# 3_Memory.net
KiCad netlist of a schematic drawn in Altium Designer
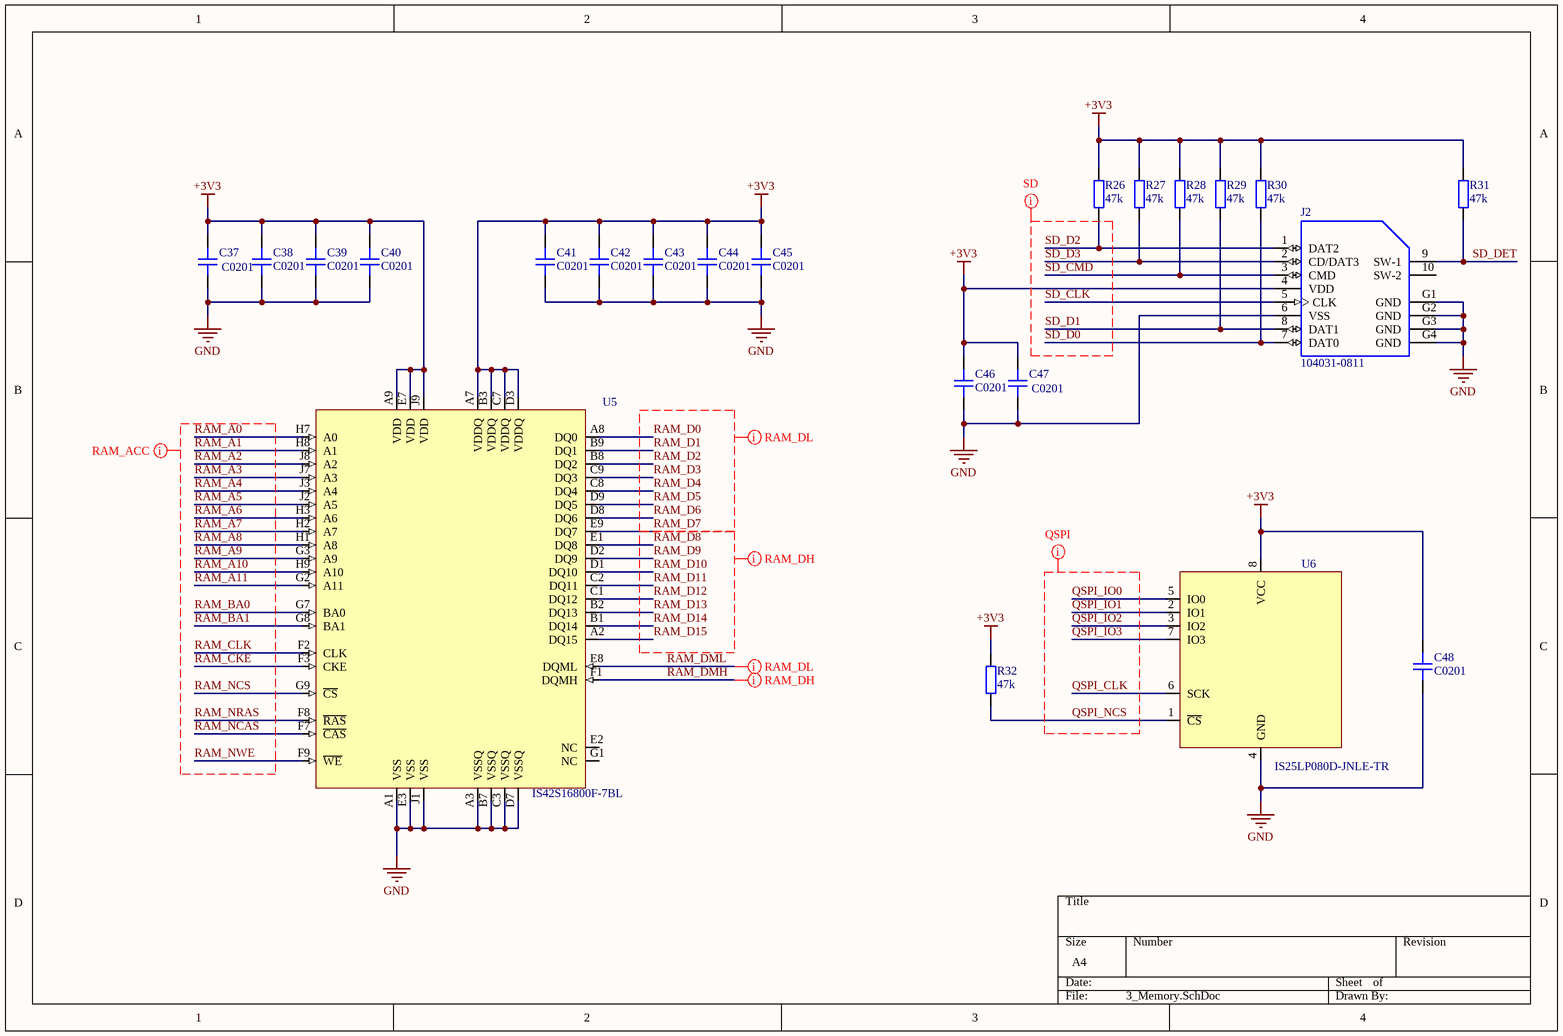
[diagram p0: 3_Memory.SchDoc]

(export (version "E")
  (design (tool "Eeschema 10.0.6"))
  (components
    (comp (ref "C37")
      (value "C0201")
      (footprint "CAP_0201")
      (description "Capacitor SMD 0201")
      (libsource (lib "Schematic-Lib-PhilsLab") (part "CAP_0201"))
    )
    (comp (ref "C38")
      (value "C0201")
      (footprint "CAP_0201")
      (description "Capacitor SMD 0201")
      (libsource (lib "Schematic-Lib-PhilsLab") (part "CAP_0201"))
    )
    (comp (ref "C39")
      (value "C0201")
      (footprint "CAP_0201")
      (description "Capacitor SMD 0201")
      (libsource (lib "Schematic-Lib-PhilsLab") (part "CAP_0201"))
    )
    (comp (ref "C40")
      (value "C0201")
      (footprint "CAP_0201")
      (description "Capacitor SMD 0201")
      (libsource (lib "Schematic-Lib-PhilsLab") (part "CAP_0201"))
    )
    (comp (ref "C41")
      (value "C0201")
      (footprint "CAP_0201")
      (description "Capacitor SMD 0201")
      (libsource (lib "Schematic-Lib-PhilsLab") (part "CAP_0201"))
    )
    (comp (ref "C42")
      (value "C0201")
      (footprint "CAP_0201")
      (description "Capacitor SMD 0201")
      (libsource (lib "Schematic-Lib-PhilsLab") (part "CAP_0201"))
    )
    (comp (ref "C43")
      (value "C0201")
      (footprint "CAP_0201")
      (description "Capacitor SMD 0201")
      (libsource (lib "Schematic-Lib-PhilsLab") (part "CAP_0201"))
    )
    (comp (ref "C44")
      (value "C0201")
      (footprint "CAP_0201")
      (description "Capacitor SMD 0201")
      (libsource (lib "Schematic-Lib-PhilsLab") (part "CAP_0201"))
    )
    (comp (ref "C45")
      (value "C0201")
      (footprint "CAP_0201")
      (description "Capacitor SMD 0201")
      (libsource (lib "Schematic-Lib-PhilsLab") (part "CAP_0201"))
    )
    (comp (ref "C46")
      (value "C0201")
      (footprint "CAP_0201")
      (description "Capacitor SMD 0201")
      (libsource (lib "Schematic-Lib-PhilsLab") (part "CAP_0201"))
    )
    (comp (ref "C47")
      (value "C0201")
      (footprint "CAP_0201")
      (description "Capacitor SMD 0201")
      (libsource (lib "Schematic-Lib-PhilsLab") (part "CAP_0201"))
    )
    (comp (ref "C48")
      (value "C0201")
      (footprint "CAP_0201")
      (description "Capacitor SMD 0201")
      (libsource (lib "Schematic-Lib-PhilsLab") (part "CAP_0201"))
    )
    (comp (ref "J2")
      (value "104031-0811")
      (footprint "104031-0811")
      (libsource (lib "SCHLib") (part "104031-0811"))
    )
    (comp (ref "R26")
      (value "47k")
      (footprint "RES_0402")
      (description "Resistor SMD 0402")
      (libsource (lib "Schematic-Lib-PhilsLab") (part "RES_0402"))
    )
    (comp (ref "R27")
      (value "47k")
      (footprint "RES_0402")
      (description "Resistor SMD 0402")
      (libsource (lib "Schematic-Lib-PhilsLab") (part "RES_0402"))
    )
    (comp (ref "R28")
      (value "47k")
      (footprint "RES_0402")
      (description "Resistor SMD 0402")
      (libsource (lib "Schematic-Lib-PhilsLab") (part "RES_0402"))
    )
    (comp (ref "R29")
      (value "47k")
      (footprint "RES_0402")
      (description "Resistor SMD 0402")
      (libsource (lib "Schematic-Lib-PhilsLab") (part "RES_0402"))
    )
    (comp (ref "R30")
      (value "47k")
      (footprint "RES_0402")
      (description "Resistor SMD 0402")
      (libsource (lib "Schematic-Lib-PhilsLab") (part "RES_0402"))
    )
    (comp (ref "R31")
      (value "47k")
      (footprint "RES_0402")
      (description "Resistor SMD 0402")
      (libsource (lib "Schematic-Lib-PhilsLab") (part "RES_0402"))
    )
    (comp (ref "R32")
      (value "47k")
      (footprint "RES_0402")
      (description "Resistor SMD 0402")
      (libsource (lib "Schematic-Lib-PhilsLab") (part "RES_0402"))
    )
    (comp (ref "U5")
      (value "IS42S16800F-7BL")
      (footprint "BGA54C80P9X9_800X800X120")
      (description "SDRAM 128Mbit 8Mx16 143Mhz 3.3V 54-ball BGA")
      (fields
        (field (name "MANUFACTURER") "ISSI")
        (field (name "MANUFACTURER PART NUMBER") "IS42S16800F-*B*")
      )
      (libsource (lib "Schematic-Lib-PhilsLab") (part "IS42S16800F-*B"))
    )
    (comp (ref "U6")
      (value "IS25LP080D-JNLE-TR")
      (footprint "SOIC-8")
      (description "QSPI NOR Flash Memory 8 Mbit SOIC-8")
      (fields (field (name "MANUFACTURER") "ISSI"))
      (libsource (lib "Schematic-Lib-PhilsLab") (part "IS25LP080D-JNLE-TR"))
    )
  )
  (nets
    (net (code "1") (name "+3V3") (class "Default")
      (node (ref "C37") (pin "2") (pinfunction "2_2") (pintype "passive"))
      (node (ref "C38") (pin "2") (pinfunction "2_2") (pintype "passive"))
      (node (ref "C39") (pin "2") (pinfunction "2_2") (pintype "passive"))
      (node (ref "C40") (pin "2") (pinfunction "2_2") (pintype "passive"))
      (node (ref "C41") (pin "2") (pinfunction "2_2") (pintype "passive"))
      (node (ref "C42") (pin "2") (pinfunction "2_2") (pintype "passive"))
      (node (ref "C43") (pin "2") (pinfunction "2_2") (pintype "passive"))
      (node (ref "C44") (pin "2") (pinfunction "2_2") (pintype "passive"))
      (node (ref "C45") (pin "2") (pinfunction "2_2") (pintype "passive"))
      (node (ref "C46") (pin "2") (pinfunction "2_2") (pintype "passive"))
      (node (ref "C47") (pin "2") (pinfunction "2_2") (pintype "passive"))
      (node (ref "C48") (pin "2") (pinfunction "2_2") (pintype "passive"))
      (node (ref "J2") (pin "4") (pinfunction "VDD_4") (pintype "power_in"))
      (node (ref "R26") (pin "2") (pinfunction "2_2") (pintype "passive"))
      (node (ref "R27") (pin "2") (pinfunction "2_2") (pintype "passive"))
      (node (ref "R28") (pin "2") (pinfunction "2_2") (pintype "passive"))
      (node (ref "R29") (pin "2") (pinfunction "2_2") (pintype "passive"))
      (node (ref "R30") (pin "2") (pinfunction "2_2") (pintype "passive"))
      (node (ref "R31") (pin "2") (pinfunction "2_2") (pintype "passive"))
      (node (ref "R32") (pin "2") (pinfunction "2_2") (pintype "passive"))
      (node (ref "U5") (pin "A7") (pinfunction "VDDQ_A7") (pintype "power_in"))
      (node (ref "U5") (pin "A9") (pinfunction "VDD_A9") (pintype "power_in"))
      (node (ref "U5") (pin "B3") (pinfunction "VDDQ_B3") (pintype "power_in"))
      (node (ref "U5") (pin "C7") (pinfunction "VDDQ_C7") (pintype "power_in"))
      (node (ref "U5") (pin "D3") (pinfunction "VDDQ_D3") (pintype "power_in"))
      (node (ref "U5") (pin "E7") (pinfunction "VDD_E7") (pintype "power_in"))
      (node (ref "U5") (pin "J9") (pinfunction "VDD_J9") (pintype "power_in"))
      (node (ref "U6") (pin "8") (pinfunction "VCC_8") (pintype "power_in"))
    )
    (net (code "2") (name "/QSPI_CLK") (class "Default")
      (node (ref "U6") (pin "6") (pinfunction "SCK_6") (pintype "passive"))
    )
    (net (code "3") (name "/QSPI_IO0") (class "Default")
      (node (ref "U6") (pin "5") (pinfunction "IO0_5") (pintype "passive"))
    )
    (net (code "4") (name "/QSPI_IO1") (class "Default")
      (node (ref "U6") (pin "2") (pinfunction "IO1_2") (pintype "passive"))
    )
    (net (code "5") (name "/QSPI_IO2") (class "Default")
      (node (ref "U6") (pin "3") (pinfunction "IO2_3") (pintype "passive"))
    )
    (net (code "6") (name "/QSPI_IO3") (class "Default")
      (node (ref "U6") (pin "7") (pinfunction "IO3_7") (pintype "passive"))
    )
    (net (code "7") (name "/QSPI_NCS") (class "Default")
      (node (ref "R32") (pin "1") (pinfunction "1_1") (pintype "passive"))
      (node (ref "U6") (pin "1") (pinfunction "~{CS}_1") (pintype "passive"))
    )
    (net (code "8") (name "/RAM_A0") (class "Default")
      (node (ref "U5") (pin "H7") (pinfunction "A0_H7") (pintype "input"))
    )
    (net (code "9") (name "/RAM_A1") (class "Default")
      (node (ref "U5") (pin "H8") (pinfunction "A1_H8") (pintype "input"))
    )
    (net (code "10") (name "/RAM_A2") (class "Default")
      (node (ref "U5") (pin "J8") (pinfunction "A2_J8") (pintype "input"))
    )
    (net (code "11") (name "/RAM_A3") (class "Default")
      (node (ref "U5") (pin "J7") (pinfunction "A3_J7") (pintype "input"))
    )
    (net (code "12") (name "/RAM_A4") (class "Default")
      (node (ref "U5") (pin "J3") (pinfunction "A4_J3") (pintype "input"))
    )
    (net (code "13") (name "/RAM_A5") (class "Default")
      (node (ref "U5") (pin "J2") (pinfunction "A5_J2") (pintype "input"))
    )
    (net (code "14") (name "/RAM_A6") (class "Default")
      (node (ref "U5") (pin "H3") (pinfunction "A6_H3") (pintype "input"))
    )
    (net (code "15") (name "/RAM_A7") (class "Default")
      (node (ref "U5") (pin "H2") (pinfunction "A7_H2") (pintype "input"))
    )
    (net (code "16") (name "/RAM_A8") (class "Default")
      (node (ref "U5") (pin "H1") (pinfunction "A8_H1") (pintype "input"))
    )
    (net (code "17") (name "/RAM_A9") (class "Default")
      (node (ref "U5") (pin "G3") (pinfunction "A9_G3") (pintype "input"))
    )
    (net (code "18") (name "/RAM_A10") (class "Default")
      (node (ref "U5") (pin "H9") (pinfunction "A10_H9") (pintype "input"))
    )
    (net (code "19") (name "/RAM_A11") (class "Default")
      (node (ref "U5") (pin "G2") (pinfunction "A11_G2") (pintype "input"))
    )
    (net (code "20") (name "/RAM_BA0") (class "Default")
      (node (ref "U5") (pin "G7") (pinfunction "BA0_G7") (pintype "input"))
    )
    (net (code "21") (name "/RAM_BA1") (class "Default")
      (node (ref "U5") (pin "G8") (pinfunction "BA1_G8") (pintype "input"))
    )
    (net (code "22") (name "/RAM_CKE") (class "Default")
      (node (ref "U5") (pin "F3") (pinfunction "CKE_F3") (pintype "input"))
    )
    (net (code "23") (name "/RAM_CLK") (class "Default")
      (node (ref "U5") (pin "F2") (pinfunction "CLK_F2") (pintype "input"))
    )
    (net (code "24") (name "/RAM_D0") (class "Default")
      (node (ref "U5") (pin "A8") (pinfunction "DQ0_A8") (pintype "bidirectional"))
    )
    (net (code "25") (name "/RAM_D1") (class "Default")
      (node (ref "U5") (pin "B9") (pinfunction "DQ1_B9") (pintype "bidirectional"))
    )
    (net (code "26") (name "/RAM_D2") (class "Default")
      (node (ref "U5") (pin "B8") (pinfunction "DQ2_B8") (pintype "bidirectional"))
    )
    (net (code "27") (name "/RAM_D3") (class "Default")
      (node (ref "U5") (pin "C9") (pinfunction "DQ3_C9") (pintype "bidirectional"))
    )
    (net (code "28") (name "/RAM_D4") (class "Default")
      (node (ref "U5") (pin "C8") (pinfunction "DQ4_C8") (pintype "bidirectional"))
    )
    (net (code "29") (name "/RAM_D5") (class "Default")
      (node (ref "U5") (pin "D9") (pinfunction "DQ5_D9") (pintype "bidirectional"))
    )
    (net (code "30") (name "/RAM_D6") (class "Default")
      (node (ref "U5") (pin "D8") (pinfunction "DQ6_D8") (pintype "bidirectional"))
    )
    (net (code "31") (name "/RAM_D7") (class "Default")
      (node (ref "U5") (pin "E9") (pinfunction "DQ7_E9") (pintype "bidirectional"))
    )
    (net (code "32") (name "/RAM_D8") (class "Default")
      (node (ref "U5") (pin "E1") (pinfunction "DQ8_E1") (pintype "bidirectional"))
    )
    (net (code "33") (name "/RAM_D9") (class "Default")
      (node (ref "U5") (pin "D2") (pinfunction "DQ9_D2") (pintype "bidirectional"))
    )
    (net (code "34") (name "/RAM_D10") (class "Default")
      (node (ref "U5") (pin "D1") (pinfunction "DQ10_D1") (pintype "bidirectional"))
    )
    (net (code "35") (name "/RAM_D11") (class "Default")
      (node (ref "U5") (pin "C2") (pinfunction "DQ11_C2") (pintype "bidirectional"))
    )
    (net (code "36") (name "/RAM_D12") (class "Default")
      (node (ref "U5") (pin "C1") (pinfunction "DQ12_C1") (pintype "bidirectional"))
    )
    (net (code "37") (name "/RAM_D13") (class "Default")
      (node (ref "U5") (pin "B2") (pinfunction "DQ13_B2") (pintype "bidirectional"))
    )
    (net (code "38") (name "/RAM_D14") (class "Default")
      (node (ref "U5") (pin "B1") (pinfunction "DQ14_B1") (pintype "bidirectional"))
    )
    (net (code "39") (name "/RAM_D15") (class "Default")
      (node (ref "U5") (pin "A2") (pinfunction "DQ15_A2") (pintype "bidirectional"))
    )
    (net (code "40") (name "/RAM_DMH") (class "Default")
      (node (ref "U5") (pin "F1") (pinfunction "DQMH_F1") (pintype "input"))
    )
    (net (code "41") (name "/RAM_DML") (class "Default")
      (node (ref "U5") (pin "E8") (pinfunction "DQML_E8") (pintype "input"))
    )
    (net (code "42") (name "/RAM_NCAS") (class "Default")
      (node (ref "U5") (pin "F7") (pinfunction "~{CAS}_F7") (pintype "input"))
    )
    (net (code "43") (name "/RAM_NCS") (class "Default")
      (node (ref "U5") (pin "G9") (pinfunction "~{CS}_G9") (pintype "input"))
    )
    (net (code "44") (name "/RAM_NRAS") (class "Default")
      (node (ref "U5") (pin "F8") (pinfunction "~{RAS}_F8") (pintype "input"))
    )
    (net (code "45") (name "/RAM_NWE") (class "Default")
      (node (ref "U5") (pin "F9") (pinfunction "~{WE}_F9") (pintype "input"))
    )
    (net (code "46") (name "/SD_CLK") (class "Default")
      (node (ref "J2") (pin "5") (pinfunction "CLK_5") (pintype "input"))
    )
    (net (code "47") (name "/SD_CMD") (class "Default")
      (node (ref "J2") (pin "3") (pinfunction "CMD_3") (pintype "bidirectional"))
      (node (ref "R28") (pin "1") (pinfunction "1_1") (pintype "passive"))
    )
    (net (code "48") (name "/SD_D0") (class "Default")
      (node (ref "J2") (pin "7") (pinfunction "DAT0_7") (pintype "bidirectional"))
      (node (ref "R30") (pin "1") (pinfunction "1_1") (pintype "passive"))
    )
    (net (code "49") (name "/SD_D1") (class "Default")
      (node (ref "J2") (pin "8") (pinfunction "DAT1_8") (pintype "bidirectional"))
      (node (ref "R29") (pin "1") (pinfunction "1_1") (pintype "passive"))
    )
    (net (code "50") (name "/SD_D2") (class "Default")
      (node (ref "J2") (pin "1") (pinfunction "DAT2_1") (pintype "bidirectional"))
      (node (ref "R26") (pin "1") (pinfunction "1_1") (pintype "passive"))
    )
    (net (code "51") (name "/SD_D3") (class "Default")
      (node (ref "J2") (pin "2") (pinfunction "CD/DAT3_2") (pintype "bidirectional"))
      (node (ref "R27") (pin "1") (pinfunction "1_1") (pintype "passive"))
    )
    (net (code "52") (name "/SD_DET") (class "Default")
      (node (ref "J2") (pin "9") (pinfunction "SW-1_9") (pintype "passive"))
      (node (ref "R31") (pin "1") (pinfunction "1_1") (pintype "passive"))
    )
    (net (code "53") (name "GND") (class "Default")
      (node (ref "C37") (pin "1") (pinfunction "1_1") (pintype "passive"))
      (node (ref "C38") (pin "1") (pinfunction "1_1") (pintype "passive"))
      (node (ref "C39") (pin "1") (pinfunction "1_1") (pintype "passive"))
      (node (ref "C40") (pin "1") (pinfunction "1_1") (pintype "passive"))
      (node (ref "C41") (pin "1") (pinfunction "1_1") (pintype "passive"))
      (node (ref "C42") (pin "1") (pinfunction "1_1") (pintype "passive"))
      (node (ref "C43") (pin "1") (pinfunction "1_1") (pintype "passive"))
      (node (ref "C44") (pin "1") (pinfunction "1_1") (pintype "passive"))
      (node (ref "C45") (pin "1") (pinfunction "1_1") (pintype "passive"))
      (node (ref "C46") (pin "1") (pinfunction "1_1") (pintype "passive"))
      (node (ref "C47") (pin "1") (pinfunction "1_1") (pintype "passive"))
      (node (ref "C48") (pin "1") (pinfunction "1_1") (pintype "passive"))
      (node (ref "J2") (pin "6") (pinfunction "VSS_6") (pintype "power_in"))
      (node (ref "J2") (pin "G1") (pinfunction "GND_G1") (pintype "power_in"))
      (node (ref "J2") (pin "G2") (pinfunction "GND_G2") (pintype "power_in"))
      (node (ref "J2") (pin "G3") (pinfunction "GND_G3") (pintype "power_in"))
      (node (ref "J2") (pin "G4") (pinfunction "GND_G4") (pintype "power_in"))
      (node (ref "U5") (pin "A1") (pinfunction "VSS_A1") (pintype "power_in"))
      (node (ref "U5") (pin "A3") (pinfunction "VSSQ_A3") (pintype "power_in"))
      (node (ref "U5") (pin "B7") (pinfunction "VSSQ_B7") (pintype "power_in"))
      (node (ref "U5") (pin "C3") (pinfunction "VSSQ_C3") (pintype "power_in"))
      (node (ref "U5") (pin "D7") (pinfunction "VSSQ_D7") (pintype "power_in"))
      (node (ref "U5") (pin "E3") (pinfunction "VSS_E3") (pintype "power_in"))
      (node (ref "U5") (pin "J1") (pinfunction "VSS_J1") (pintype "power_in"))
      (node (ref "U6") (pin "4") (pinfunction "GND_4") (pintype "power_in"))
    )
    (net (code "54") (name "unconnected-(J2-SW-2-Pad10)") (class "Default")
      (node (ref "J2") (pin "10") (pinfunction "SW-2_10") (pintype "passive"))
    )
    (net (code "55") (name "unconnected-(U5-NC-PadE2)") (class "Default")
      (node (ref "U5") (pin "E2") (pinfunction "NC_E2") (pintype "passive"))
    )
    (net (code "56") (name "unconnected-(U5-NC-PadG1)") (class "Default")
      (node (ref "U5") (pin "G1") (pinfunction "NC_G1") (pintype "passive"))
    )
  )
)
